# Sheet1.net
KiCad netlist of a schematic drawn in Altium Designer
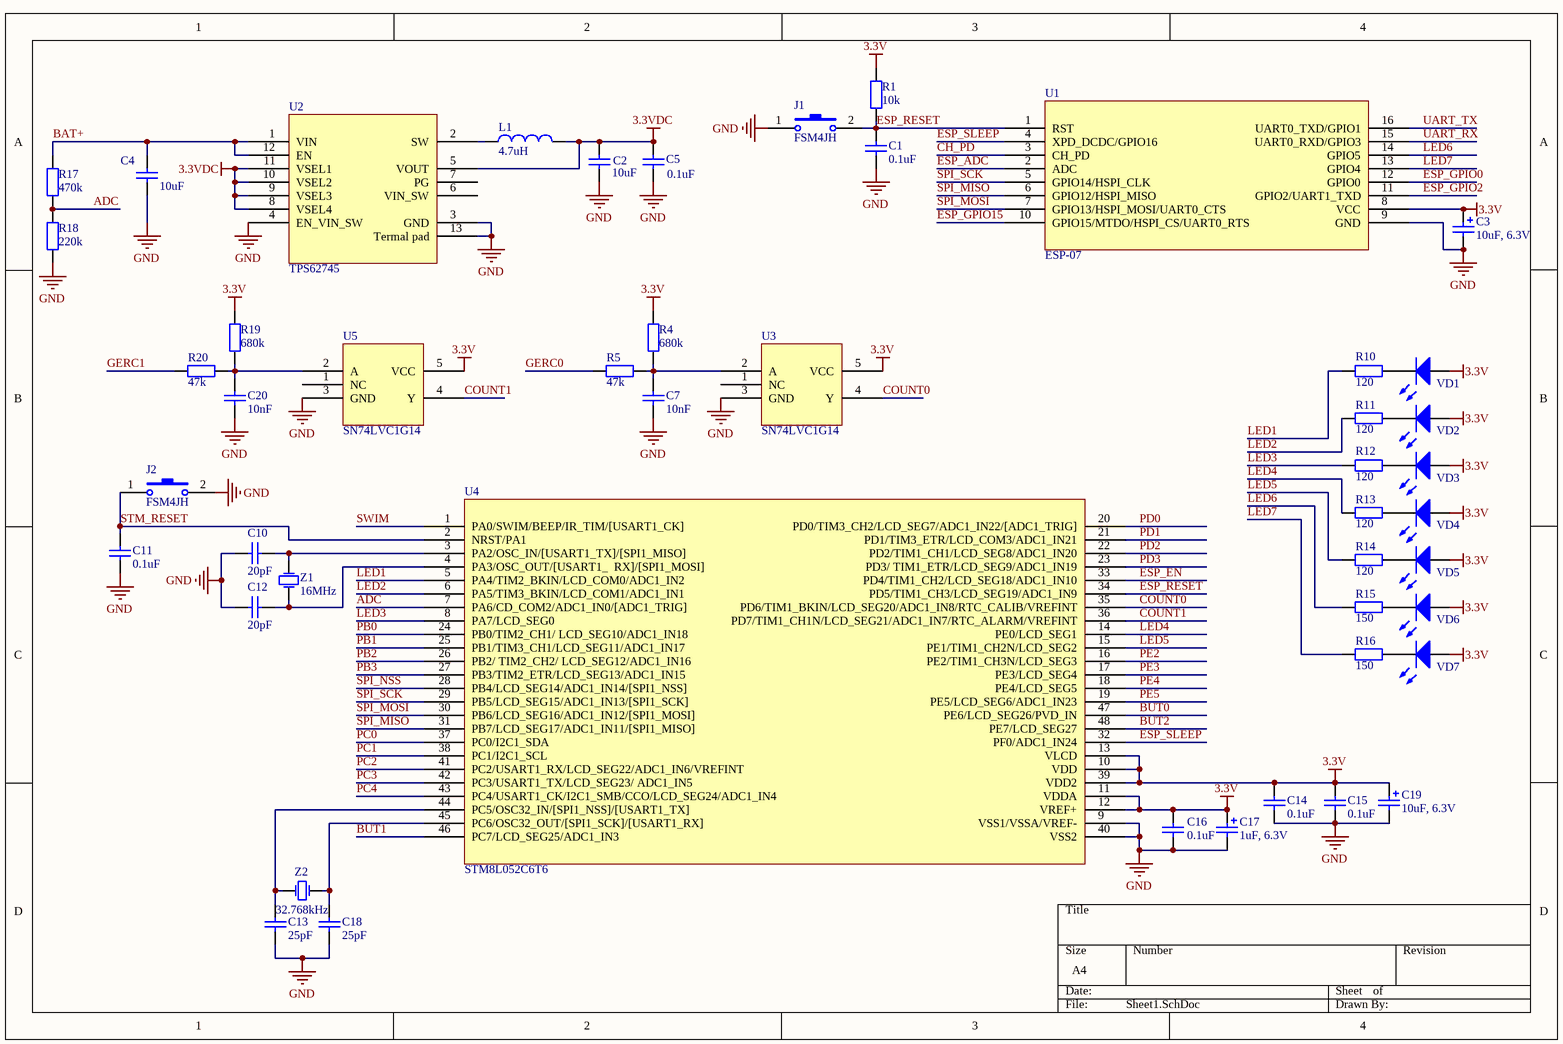
[diagram p0: Sheet1.SchDoc]

(export (version "E")
  (design (tool "Eeschema 10.0.6"))
  (components
    (comp (ref "C1")
      (value "0.1uF")
      (footprint "0603(CAPC1608X09N)")
      (description "Capacitor")
      (libsource (lib "Passive") (part "Capacitor"))
    )
    (comp (ref "C2")
      (value "10uF")
      (footprint "1206(CAPC3216X15N)")
      (description "Capacitor")
      (libsource (lib "Passive") (part "Capacitor"))
    )
    (comp (ref "C3")
      (value "10uF, 6.3V")
      (footprint "1206(typeA)")
      (description "Polarized Capacitor")
      (fields (field (name "Comment") "Capacitor Polarized"))
      (libsource (lib "Passive") (part "Polarized Capacitor"))
    )
    (comp (ref "C4")
      (value "10uF")
      (footprint "1206(CAPC3216X15N)")
      (description "Capacitor")
      (libsource (lib "Passive") (part "Capacitor"))
    )
    (comp (ref "C5")
      (value "0.1uF")
      (footprint "0603(CAPC1608X09N)")
      (description "Capacitor")
      (libsource (lib "Passive") (part "Capacitor"))
    )
    (comp (ref "C7")
      (value "10nF")
      (footprint "0603(CAPC1608X09N)")
      (description "Capacitor")
      (libsource (lib "Passive") (part "Capacitor"))
    )
    (comp (ref "C10")
      (value "20pF")
      (footprint "0603(CAPC1608X09N)")
      (description "Capacitor")
      (libsource (lib "Passive") (part "Capacitor"))
    )
    (comp (ref "C11")
      (value "0.1uF")
      (footprint "0603(CAPC1608X09N)")
      (description "Capacitor")
      (libsource (lib "Passive") (part "Capacitor"))
    )
    (comp (ref "C12")
      (value "20pF")
      (footprint "0603(CAPC1608X09N)")
      (description "Capacitor")
      (libsource (lib "Passive") (part "Capacitor"))
    )
    (comp (ref "C13")
      (value "25pF")
      (footprint "0603(CAPC1608X09N)")
      (description "Capacitor")
      (libsource (lib "Passive") (part "Capacitor"))
    )
    (comp (ref "C14")
      (value "0.1uF")
      (footprint "0603(CAPC1608X09N)")
      (description "Capacitor")
      (libsource (lib "Passive") (part "Capacitor"))
    )
    (comp (ref "C15")
      (value "0.1uF")
      (footprint "0603(CAPC1608X09N)")
      (description "Capacitor")
      (libsource (lib "Passive") (part "Capacitor"))
    )
    (comp (ref "C16")
      (value "0.1uF")
      (footprint "0603(CAPC1608X09N)")
      (description "Capacitor")
      (libsource (lib "Passive") (part "Capacitor"))
    )
    (comp (ref "C17")
      (value "1uF, 6.3V")
      (footprint "1206(typeA)")
      (description "Polarized Capacitor")
      (fields (field (name "Comment") "Capacitor Polarized"))
      (libsource (lib "Passive") (part "Polarized Capacitor"))
    )
    (comp (ref "C18")
      (value "25pF")
      (footprint "0603(CAPC1608X09N)")
      (description "Capacitor")
      (libsource (lib "Passive") (part "Capacitor"))
    )
    (comp (ref "C19")
      (value "10uF, 6.3V")
      (footprint "1206(typeA)")
      (description "Polarized Capacitor")
      (fields (field (name "Comment") "Capacitor Polarized"))
      (libsource (lib "Passive") (part "Polarized Capacitor"))
    )
    (comp (ref "C20")
      (value "10nF")
      (footprint "0603(CAPC1608X09N)")
      (description "Capacitor")
      (libsource (lib "Passive") (part "Capacitor"))
    )
    (comp (ref "J1")
      (value "FSM4JH")
      (footprint "FSM4JH")
      (description "Tact switch")
      (libsource (lib "Schlib1") (part "Tact switch"))
    )
    (comp (ref "J2")
      (value "FSM4JH")
      (footprint "FSM4JH")
      (description "Tact switch")
      (libsource (lib "Schlib1") (part "Tact switch"))
    )
    (comp (ref "L1")
      (value "4.7uH")
      (footprint "0806 (2016)")
      (description "Inductor")
      (libsource (lib "Passive") (part "Inductor"))
    )
    (comp (ref "R1")
      (value "10k")
      (footprint "0603(RESC1608X05N)")
      (description "Resistor")
      (libsource (lib "") (part "Resistor_2"))
    )
    (comp (ref "R4")
      (value "680k")
      (footprint "0603(RESC1608X05N)")
      (description "Resistor")
      (libsource (lib "") (part "Resistor_2"))
    )
    (comp (ref "R5")
      (value "47k")
      (footprint "0603(RESC1608X05N)")
      (description "Resistor")
      (libsource (lib "") (part "Resistor_1"))
    )
    (comp (ref "R10")
      (value "120")
      (footprint "0603(RESC1608X05N)")
      (description "Resistor")
      (libsource (lib "Passive") (part "Resistor"))
    )
    (comp (ref "R11")
      (value "120")
      (footprint "0603(RESC1608X05N)")
      (description "Resistor")
      (libsource (lib "Passive") (part "Resistor"))
    )
    (comp (ref "R12")
      (value "120")
      (footprint "0603(RESC1608X05N)")
      (description "Resistor")
      (libsource (lib "Passive") (part "Resistor"))
    )
    (comp (ref "R13")
      (value "120")
      (footprint "0603(RESC1608X05N)")
      (description "Resistor")
      (libsource (lib "Passive") (part "Resistor"))
    )
    (comp (ref "R14")
      (value "120")
      (footprint "0603(RESC1608X05N)")
      (description "Resistor")
      (libsource (lib "Passive") (part "Resistor"))
    )
    (comp (ref "R15")
      (value "150")
      (footprint "0603(RESC1608X05N)")
      (description "Resistor")
      (libsource (lib "Passive") (part "Resistor"))
    )
    (comp (ref "R16")
      (value "150")
      (footprint "0603(RESC1608X05N)")
      (description "Resistor")
      (libsource (lib "Passive") (part "Resistor"))
    )
    (comp (ref "R17")
      (value "470k")
      (footprint "0603(RESC1608X05N)")
      (description "Resistor")
      (libsource (lib "") (part "Resistor_2"))
    )
    (comp (ref "R18")
      (value "220k")
      (footprint "0603(RESC1608X05N)")
      (description "Resistor")
      (libsource (lib "") (part "Resistor_2"))
    )
    (comp (ref "R19")
      (value "680k")
      (footprint "0603(RESC1608X05N)")
      (description "Resistor")
      (libsource (lib "") (part "Resistor_2"))
    )
    (comp (ref "R20")
      (value "47k")
      (footprint "0603(RESC1608X05N)")
      (description "Resistor")
      (libsource (lib "") (part "Resistor_1"))
    )
    (comp (ref "U1")
      (value "ESP-07")
      (footprint "ESP-07")
      (description "WiFi module")
      (libsource (lib "Schlib1") (part "ESP-07"))
    )
    (comp (ref "U2")
      (value "TPS62745")
      (footprint "12-WSON (3x2)")
      (description "DC/DC step down")
      (fields (field (name "PART NUMBER") "TPS62745DSST") (field (name "MANUFACTURER") "Texas Instruments"))
      (libsource (lib "Schlib1") (part "TPS62745"))
    )
    (comp (ref "U3")
      (value "SN74LVC1G14")
      (footprint "SOT23-5")
      (description "Single SchmittT-Trigger Inverter")
      (fields
        (field (name "PART NUMBER") "SN74LVC1G14DBVR")
        (field (name "MANUFACTURER") "Texas Instruments")
      )
      (libsource (lib "Schlib1") (part "SN74LVC1G14"))
    )
    (comp (ref "U4")
      (value "STM8L052C6T6")
      (footprint "LQFP-48")
      (description "MCU")
      (fields (field (name "MANUFACTURER") "STMicroelectronics"))
      (libsource (lib "Schlib1") (part "STM8L052C6"))
    )
    (comp (ref "U5")
      (value "SN74LVC1G14")
      (footprint "SOT23-5")
      (description "Single SchmittT-Trigger Inverter")
      (fields
        (field (name "PART NUMBER") "SN74LVC1G14DBVR")
        (field (name "MANUFACTURER") "Texas Instruments")
      )
      (libsource (lib "Schlib1") (part "SN74LVC1G14"))
    )
    (comp (ref "VD1")
      (value "Led")
      (footprint "GNL-3014xx")
      (description "Светодиод")
      (libsource (lib "Passive") (part "Led"))
    )
    (comp (ref "VD2")
      (value "Led")
      (footprint "GNL-3014xx")
      (description "Светодиод")
      (libsource (lib "Passive") (part "Led"))
    )
    (comp (ref "VD3")
      (value "Led")
      (footprint "GNL-3014xx")
      (description "Светодиод")
      (libsource (lib "Passive") (part "Led"))
    )
    (comp (ref "VD4")
      (value "Led")
      (footprint "GNL-3014xx")
      (description "Светодиод")
      (libsource (lib "Passive") (part "Led"))
    )
    (comp (ref "VD5")
      (value "Led")
      (footprint "GNL-3014xx")
      (description "Светодиод")
      (libsource (lib "Passive") (part "Led"))
    )
    (comp (ref "VD6")
      (value "Led")
      (footprint "GNL-3014xx")
      (description "Светодиод")
      (libsource (lib "Passive") (part "Led"))
    )
    (comp (ref "VD7")
      (value "Led")
      (footprint "GNL-3014xx")
      (description "Светодиод")
      (libsource (lib "Passive") (part "Led"))
    )
    (comp (ref "Z1")
      (value "16MHz")
      (footprint "HC49S")
      (description "Crystal Oscillator")
      (libsource (lib "Passive") (part "Crystal"))
    )
    (comp (ref "Z2")
      (value "32.768kHz")
      (footprint "KX–327NHT")
      (description "Crystal Oscillator")
      (libsource (lib "Passive") (part "Crystal"))
    )
  )
  (nets
    (net (code "1") (name "/ADC") (class "Default")
      (node (ref "R17") (pin "1") (pinfunction "1_1") (pintype "passive"))
      (node (ref "R18") (pin "2") (pinfunction "2_2") (pintype "passive"))
      (node (ref "U4") (pin "7") (pinfunction "PA6/CD_COM2/ADC1_IN0/[ADC1_TRIG]_7") (pintype "passive"))
    )
    (net (code "2") (name "/BAT+") (class "Default")
      (node (ref "C4") (pin "1") (pinfunction "1_1") (pintype "passive"))
      (node (ref "R17") (pin "2") (pinfunction "2_2") (pintype "passive"))
      (node (ref "U2") (pin "1") (pinfunction "VIN_1") (pintype "passive"))
      (node (ref "U2") (pin "12") (pinfunction "EN_12") (pintype "passive"))
    )
    (net (code "3") (name "/BUT0") (class "Default")
      (node (ref "U4") (pin "47") (pinfunction "PE6/LCD_SEG26/PVD_IN_47") (pintype "passive"))
    )
    (net (code "4") (name "/BUT1") (class "Default")
      (node (ref "U4") (pin "46") (pinfunction "PC7/LCD_SEG25/ADC1_IN3_46") (pintype "passive"))
    )
    (net (code "5") (name "/BUT2") (class "Default")
      (node (ref "U4") (pin "48") (pinfunction "PE7/LCD_SEG27_48") (pintype "passive"))
    )
    (net (code "6") (name "/CH_PD") (class "Default")
      (node (ref "U1") (pin "3") (pinfunction "CH_PD_3") (pintype "passive"))
    )
    (net (code "7") (name "/COUNT0") (class "Default")
      (node (ref "U3") (pin "4") (pinfunction "Y_4") (pintype "passive"))
      (node (ref "U4") (pin "35") (pinfunction "PD6/TIM1_BKIN/LCD_SEG20/ADC1_IN8/RTC_CALIB/VREFINT_35") (pintype "passive"))
    )
    (net (code "8") (name "/COUNT1") (class "Default")
      (node (ref "U4") (pin "36") (pinfunction "PD7/TIM1_CH1N/LCD_SEG21/ADC1_IN7/RTC_ALARM/VREFINT_36") (pintype "passive"))
      (node (ref "U5") (pin "4") (pinfunction "Y_4") (pintype "passive"))
    )
    (net (code "9") (name "/ESP_ADC") (class "Default")
      (node (ref "U1") (pin "2") (pinfunction "ADC_2") (pintype "passive"))
    )
    (net (code "10") (name "/ESP_EN") (class "Default")
      (node (ref "U4") (pin "33") (pinfunction "PD4/TIM1_CH2/LCD_SEG18/ADC1_IN10_33") (pintype "passive"))
    )
    (net (code "11") (name "/ESP_GPIO0") (class "Default")
      (node (ref "U1") (pin "12") (pinfunction "GPIO0_12") (pintype "passive"))
    )
    (net (code "12") (name "/ESP_GPIO2") (class "Default")
      (node (ref "U1") (pin "11") (pinfunction "GPIO2/UART1_TXD_11") (pintype "passive"))
    )
    (net (code "13") (name "/ESP_GPIO15") (class "Default")
      (node (ref "U1") (pin "10") (pinfunction "GPIO15/MTDO/HSPI_CS/UART0_RTS_10") (pintype "passive"))
    )
    (net (code "14") (name "/ESP_RESET") (class "Default")
      (node (ref "C1") (pin "2") (pinfunction "2_2") (pintype "passive"))
      (node (ref "J1") (pin "2") (pinfunction "NO1_2") (pintype "passive"))
      (node (ref "R1") (pin "1") (pinfunction "1_1") (pintype "passive"))
      (node (ref "U1") (pin "1") (pinfunction "RST_1") (pintype "passive"))
      (node (ref "U4") (pin "34") (pinfunction "PD5/TIM1_CH3/LCD_SEG19/ADC1_IN9_34") (pintype "passive"))
    )
    (net (code "15") (name "/ESP_SLEEP") (class "Default")
      (node (ref "U1") (pin "4") (pinfunction "XPD_DCDC/GPIO16_4") (pintype "passive"))
      (node (ref "U4") (pin "32") (pinfunction "PF0/ADC1_IN24_32") (pintype "passive"))
    )
    (net (code "16") (name "/GERC0") (class "Default")
      (node (ref "R5") (pin "2") (pinfunction "2_2") (pintype "passive"))
    )
    (net (code "17") (name "/GERC1") (class "Default")
      (node (ref "R20") (pin "2") (pinfunction "2_2") (pintype "passive"))
    )
    (net (code "18") (name "/LED1") (class "Default")
      (node (ref "R10") (pin "1") (pinfunction "1_1") (pintype "passive"))
      (node (ref "U4") (pin "5") (pinfunction "PA4/TIM2_BKIN/LCD_COM0/ADC1_IN2_5") (pintype "passive"))
    )
    (net (code "19") (name "/LED2") (class "Default")
      (node (ref "R11") (pin "1") (pinfunction "1_1") (pintype "passive"))
      (node (ref "U4") (pin "6") (pinfunction "PA5/TIM3_BKIN/LCD_COM1/ADC1_IN1_6") (pintype "passive"))
    )
    (net (code "20") (name "/LED3") (class "Default")
      (node (ref "R12") (pin "1") (pinfunction "1_1") (pintype "passive"))
      (node (ref "U4") (pin "8") (pinfunction "PA7/LCD_SEG0_8") (pintype "passive"))
    )
    (net (code "21") (name "/LED4") (class "Default")
      (node (ref "R13") (pin "1") (pinfunction "1_1") (pintype "passive"))
      (node (ref "U4") (pin "14") (pinfunction "PE0/LCD_SEG1_14") (pintype "passive"))
    )
    (net (code "22") (name "/LED5") (class "Default")
      (node (ref "R14") (pin "1") (pinfunction "1_1") (pintype "passive"))
      (node (ref "U4") (pin "15") (pinfunction "PE1/TIM1_CH2N/LCD_SEG2_15") (pintype "passive"))
    )
    (net (code "23") (name "/LED6") (class "Default")
      (node (ref "R15") (pin "1") (pinfunction "1_1") (pintype "passive"))
      (node (ref "U1") (pin "14") (pinfunction "GPIO5_14") (pintype "passive"))
    )
    (net (code "24") (name "/LED7") (class "Default")
      (node (ref "R16") (pin "1") (pinfunction "1_1") (pintype "passive"))
      (node (ref "U1") (pin "13") (pinfunction "GPIO4_13") (pintype "passive"))
    )
    (net (code "25") (name "/PB0") (class "Default")
      (node (ref "U4") (pin "24") (pinfunction "PB0/TIM2_CH1/_LCD_SEG10/ADC1_IN18_24") (pintype "passive"))
    )
    (net (code "26") (name "/PB1") (class "Default")
      (node (ref "U4") (pin "25") (pinfunction "PB1/TIM3_CH1/LCD_SEG11/ADC1_IN17_25") (pintype "passive"))
    )
    (net (code "27") (name "/PB2") (class "Default")
      (node (ref "U4") (pin "26") (pinfunction "PB2/_TIM2_CH2/_LCD_SEG12/ADC1_IN16_26") (pintype "passive"))
    )
    (net (code "28") (name "/PB3") (class "Default")
      (node (ref "U4") (pin "27") (pinfunction "PB3/TIM2_ETR/LCD_SEG13/ADC1_IN15_27") (pintype "passive"))
    )
    (net (code "29") (name "/PC0") (class "Default")
      (node (ref "U4") (pin "37") (pinfunction "PC0/I2C1_SDA_37") (pintype "passive"))
    )
    (net (code "30") (name "/PC1") (class "Default")
      (node (ref "U4") (pin "38") (pinfunction "PC1/I2C1_SCL_38") (pintype "passive"))
    )
    (net (code "31") (name "/PC2") (class "Default")
      (node (ref "U4") (pin "41") (pinfunction "PC2/USART1_RX/LCD_SEG22/ADC1_IN6/VREFINT_41") (pintype "passive"))
    )
    (net (code "32") (name "/PC3") (class "Default")
      (node (ref "U4") (pin "42") (pinfunction "PC3/USART1_TX/LCD_SEG23/_ADC1_IN5_42") (pintype "passive"))
    )
    (net (code "33") (name "/PC4") (class "Default")
      (node (ref "U4") (pin "43") (pinfunction "PC4/USART1_CK/I2C1_SMB/CCO/LCD_SEG24/ADC1_IN4_43") (pintype "passive"))
    )
    (net (code "34") (name "/PD0") (class "Default")
      (node (ref "U4") (pin "20") (pinfunction "PD0/TIM3_CH2/LCD_SEG7/ADC1_IN22/[ADC1_TRIG]_20") (pintype "passive"))
    )
    (net (code "35") (name "/PD1") (class "Default")
      (node (ref "U4") (pin "21") (pinfunction "PD1/TIM3_ETR/LCD_COM3/ADC1_IN21_21") (pintype "passive"))
    )
    (net (code "36") (name "/PD2") (class "Default")
      (node (ref "U4") (pin "22") (pinfunction "PD2/TIM1_CH1/LCD_SEG8/ADC1_IN20_22") (pintype "passive"))
    )
    (net (code "37") (name "/PD3") (class "Default")
      (node (ref "U4") (pin "23") (pinfunction "PD3/_TIM1_ETR/LCD_SEG9/ADC1_IN19_23") (pintype "passive"))
    )
    (net (code "38") (name "/PE2") (class "Default")
      (node (ref "U4") (pin "16") (pinfunction "PE2/TIM1_CH3N/LCD_SEG3_16") (pintype "passive"))
    )
    (net (code "39") (name "/PE3") (class "Default")
      (node (ref "U4") (pin "17") (pinfunction "PE3/LCD_SEG4_17") (pintype "passive"))
    )
    (net (code "40") (name "/PE4") (class "Default")
      (node (ref "U4") (pin "18") (pinfunction "PE4/LCD_SEG5_18") (pintype "passive"))
    )
    (net (code "41") (name "/PE5") (class "Default")
      (node (ref "U4") (pin "19") (pinfunction "PE5/LCD_SEG6/ADC1_IN23_19") (pintype "passive"))
    )
    (net (code "42") (name "/SPI_MISO") (class "Default")
      (node (ref "U1") (pin "6") (pinfunction "GPIO12/HSPI_MISO_6") (pintype "passive"))
      (node (ref "U4") (pin "31") (pinfunction "PB7/LCD_SEG17/ADC1_IN11/[SPI1_MISO]_31") (pintype "passive"))
    )
    (net (code "43") (name "/SPI_MOSI") (class "Default")
      (node (ref "U1") (pin "7") (pinfunction "GPIO13/HSPI_MOSI/UART0_CTS_7") (pintype "passive"))
      (node (ref "U4") (pin "30") (pinfunction "PB6/LCD_SEG16/ADC1_IN12/[SPI1_MOSI]_30") (pintype "passive"))
    )
    (net (code "44") (name "/SPI_NSS") (class "Default")
      (node (ref "U4") (pin "28") (pinfunction "PB4/LCD_SEG14/ADC1_IN14/[SPI1_NSS]_28") (pintype "passive"))
    )
    (net (code "45") (name "/SPI_SCK") (class "Default")
      (node (ref "U1") (pin "5") (pinfunction "GPIO14/HSPI_CLK_5") (pintype "passive"))
      (node (ref "U4") (pin "29") (pinfunction "PB5/LCD_SEG15/ADC1_IN13/[SPI1_SCK]_29") (pintype "passive"))
    )
    (net (code "46") (name "/STM_RESET") (class "Default")
      (node (ref "C11") (pin "2") (pinfunction "2_2") (pintype "passive"))
      (node (ref "J2") (pin "1") (pinfunction "COMMON1_1") (pintype "passive"))
      (node (ref "U4") (pin "2") (pinfunction "NRST/PA1_2") (pintype "passive"))
    )
    (net (code "47") (name "/SWIM") (class "Default")
      (node (ref "U4") (pin "1") (pinfunction "PA0/SWIM/BEEP/IR_TIM/[USART1_CK]_1") (pintype "passive"))
    )
    (net (code "48") (name "/UART_RX") (class "Default")
      (node (ref "U1") (pin "15") (pinfunction "UART0_RXD/GPIO3_15") (pintype "passive"))
    )
    (net (code "49") (name "/UART_TX") (class "Default")
      (node (ref "U1") (pin "16") (pinfunction "UART0_TXD/GPIO1_16") (pintype "passive"))
    )
    (net (code "50") (name "3.3V") (class "Default")
      (node (ref "C14") (pin "2") (pinfunction "2_2") (pintype "passive"))
      (node (ref "C15") (pin "2") (pinfunction "2_2") (pintype "passive"))
      (node (ref "C16") (pin "1") (pinfunction "1_1") (pintype "passive"))
      (node (ref "C17") (pin "1") (pinfunction "1_1") (pintype "passive"))
      (node (ref "C19") (pin "1") (pinfunction "1_1") (pintype "passive"))
      (node (ref "C3") (pin "1") (pinfunction "1_1") (pintype "passive"))
      (node (ref "R1") (pin "2") (pinfunction "2_2") (pintype "passive"))
      (node (ref "R19") (pin "2") (pinfunction "2_2") (pintype "passive"))
      (node (ref "R4") (pin "2") (pinfunction "2_2") (pintype "passive"))
      (node (ref "U1") (pin "8") (pinfunction "VCC_8") (pintype "passive"))
      (node (ref "U3") (pin "5") (pinfunction "VCC_5") (pintype "passive"))
      (node (ref "U4") (pin "10") (pinfunction "VDD_10") (pintype "passive"))
      (node (ref "U4") (pin "11") (pinfunction "VDDA_11") (pintype "passive"))
      (node (ref "U4") (pin "12") (pinfunction "VREF+_12") (pintype "passive"))
      (node (ref "U4") (pin "13") (pinfunction "VLCD_13") (pintype "passive"))
      (node (ref "U4") (pin "39") (pinfunction "VDD2_39") (pintype "passive"))
      (node (ref "U5") (pin "5") (pinfunction "VCC_5") (pintype "passive"))
      (node (ref "VD1") (pin "1") (pinfunction "A_1") (pintype "passive"))
      (node (ref "VD2") (pin "1") (pinfunction "A_1") (pintype "passive"))
      (node (ref "VD3") (pin "1") (pinfunction "A_1") (pintype "passive"))
      (node (ref "VD4") (pin "1") (pinfunction "A_1") (pintype "passive"))
      (node (ref "VD5") (pin "1") (pinfunction "A_1") (pintype "passive"))
      (node (ref "VD6") (pin "1") (pinfunction "A_1") (pintype "passive"))
      (node (ref "VD7") (pin "1") (pinfunction "A_1") (pintype "passive"))
    )
    (net (code "51") (name "3.3VDC") (class "Default")
      (node (ref "C2") (pin "2") (pinfunction "2_2") (pintype "passive"))
      (node (ref "C5") (pin "2") (pinfunction "2_2") (pintype "passive"))
      (node (ref "L1") (pin "1") (pinfunction "1_1") (pintype "passive"))
      (node (ref "U2") (pin "10") (pinfunction "VSEL2_10") (pintype "passive"))
      (node (ref "U2") (pin "11") (pinfunction "VSEL1_11") (pintype "passive"))
      (node (ref "U2") (pin "5") (pinfunction "VOUT_5") (pintype "passive"))
      (node (ref "U2") (pin "8") (pinfunction "VSEL4_8") (pintype "passive"))
      (node (ref "U2") (pin "9") (pinfunction "VSEL3_9") (pintype "passive"))
    )
    (net (code "52") (name "GND") (class "Default")
      (node (ref "C1") (pin "1") (pinfunction "1_1") (pintype "passive"))
      (node (ref "C10") (pin "1") (pinfunction "1_1") (pintype "passive"))
      (node (ref "C11") (pin "1") (pinfunction "1_1") (pintype "passive"))
      (node (ref "C12") (pin "1") (pinfunction "1_1") (pintype "passive"))
      (node (ref "C13") (pin "1") (pinfunction "1_1") (pintype "passive"))
      (node (ref "C14") (pin "1") (pinfunction "1_1") (pintype "passive"))
      (node (ref "C15") (pin "1") (pinfunction "1_1") (pintype "passive"))
      (node (ref "C16") (pin "2") (pinfunction "2_2") (pintype "passive"))
      (node (ref "C17") (pin "2") (pinfunction "2_2") (pintype "passive"))
      (node (ref "C18") (pin "1") (pinfunction "1_1") (pintype "passive"))
      (node (ref "C19") (pin "2") (pinfunction "2_2") (pintype "passive"))
      (node (ref "C2") (pin "1") (pinfunction "1_1") (pintype "passive"))
      (node (ref "C20") (pin "1") (pinfunction "1_1") (pintype "passive"))
      (node (ref "C3") (pin "2") (pinfunction "2_2") (pintype "passive"))
      (node (ref "C4") (pin "2") (pinfunction "2_2") (pintype "passive"))
      (node (ref "C5") (pin "1") (pinfunction "1_1") (pintype "passive"))
      (node (ref "C7") (pin "1") (pinfunction "1_1") (pintype "passive"))
      (node (ref "J1") (pin "1") (pinfunction "COMMON1_1") (pintype "passive"))
      (node (ref "J2") (pin "2") (pinfunction "NO1_2") (pintype "passive"))
      (node (ref "R18") (pin "1") (pinfunction "1_1") (pintype "passive"))
      (node (ref "U1") (pin "9") (pinfunction "GND_9") (pintype "passive"))
      (node (ref "U2") (pin "13") (pinfunction "Termal_pad_13") (pintype "passive"))
      (node (ref "U2") (pin "3") (pinfunction "GND_3") (pintype "passive"))
      (node (ref "U2") (pin "4") (pinfunction "EN_VIN_SW_4") (pintype "passive"))
      (node (ref "U3") (pin "3") (pinfunction "GND_3") (pintype "passive"))
      (node (ref "U4") (pin "40") (pinfunction "VSS2_40") (pintype "passive"))
      (node (ref "U4") (pin "9") (pinfunction "VSS1/VSSA/VREF-_9") (pintype "passive"))
      (node (ref "U5") (pin "3") (pinfunction "GND_3") (pintype "passive"))
    )
    (net (code "53") (name "Net-(U2-SW)") (class "Default")
      (node (ref "L1") (pin "2") (pinfunction "2_2") (pintype "passive"))
      (node (ref "U2") (pin "2") (pinfunction "SW_2") (pintype "passive"))
    )
    (net (code "54") (name "Net-(U3-A)") (class "Default")
      (node (ref "C7") (pin "2") (pinfunction "2_2") (pintype "passive"))
      (node (ref "R4") (pin "1") (pinfunction "1_1") (pintype "passive"))
      (node (ref "R5") (pin "1") (pinfunction "1_1") (pintype "passive"))
      (node (ref "U3") (pin "2") (pinfunction "A_2") (pintype "passive"))
    )
    (net (code "55") (name "Net-(U4-PA2{slash}OSC_IN{slash}[USART1_TX]{slash}[SPI1_MISO])") (class "Default")
      (node (ref "C10") (pin "2") (pinfunction "2_2") (pintype "passive"))
      (node (ref "U4") (pin "3") (pinfunction "PA2/OSC_IN/[USART1_TX]/[SPI1_MISO]_3") (pintype "passive"))
      (node (ref "Z1") (pin "2") (pinfunction "OSC2_2") (pintype "passive"))
    )
    (net (code "56") (name "Net-(U4-PA3{slash}OSC_OUT{slash}[USART1___RX]{slash}[SPI1_MOSI])") (class "Default")
      (node (ref "C12") (pin "2") (pinfunction "2_2") (pintype "passive"))
      (node (ref "U4") (pin "4") (pinfunction "PA3/OSC_OUT/[USART1___RX]/[SPI1_MOSI]_4") (pintype "passive"))
      (node (ref "Z1") (pin "1") (pinfunction "OSC1_1") (pintype "passive"))
    )
    (net (code "57") (name "Net-(U4-PC5{slash}OSC32_IN{slash}[SPI1_NSS]{slash}[USART1_TX])") (class "Default")
      (node (ref "C13") (pin "2") (pinfunction "2_2") (pintype "passive"))
      (node (ref "U4") (pin "44") (pinfunction "PC5/OSC32_IN/[SPI1_NSS]/[USART1_TX]_44") (pintype "passive"))
      (node (ref "Z2") (pin "2") (pinfunction "OSC2_2") (pintype "passive"))
    )
    (net (code "58") (name "Net-(U4-PC6{slash}OSC32_OUT{slash}[SPI1_SCK]{slash}[USART1_RX])") (class "Default")
      (node (ref "C18") (pin "2") (pinfunction "2_2") (pintype "passive"))
      (node (ref "U4") (pin "45") (pinfunction "PC6/OSC32_OUT/[SPI1_SCK]/[USART1_RX]_45") (pintype "passive"))
      (node (ref "Z2") (pin "1") (pinfunction "OSC1_1") (pintype "passive"))
    )
    (net (code "59") (name "Net-(U5-A)") (class "Default")
      (node (ref "C20") (pin "2") (pinfunction "2_2") (pintype "passive"))
      (node (ref "R19") (pin "1") (pinfunction "1_1") (pintype "passive"))
      (node (ref "R20") (pin "1") (pinfunction "1_1") (pintype "passive"))
      (node (ref "U5") (pin "2") (pinfunction "A_2") (pintype "passive"))
    )
    (net (code "60") (name "Net-(VD1-K)") (class "Default")
      (node (ref "R10") (pin "2") (pinfunction "2_2") (pintype "passive"))
      (node (ref "VD1") (pin "2") (pinfunction "K_2") (pintype "passive"))
    )
    (net (code "61") (name "Net-(VD2-K)") (class "Default")
      (node (ref "R11") (pin "2") (pinfunction "2_2") (pintype "passive"))
      (node (ref "VD2") (pin "2") (pinfunction "K_2") (pintype "passive"))
    )
    (net (code "62") (name "Net-(VD3-K)") (class "Default")
      (node (ref "R12") (pin "2") (pinfunction "2_2") (pintype "passive"))
      (node (ref "VD3") (pin "2") (pinfunction "K_2") (pintype "passive"))
    )
    (net (code "63") (name "Net-(VD4-K)") (class "Default")
      (node (ref "R13") (pin "2") (pinfunction "2_2") (pintype "passive"))
      (node (ref "VD4") (pin "2") (pinfunction "K_2") (pintype "passive"))
    )
    (net (code "64") (name "Net-(VD5-K)") (class "Default")
      (node (ref "R14") (pin "2") (pinfunction "2_2") (pintype "passive"))
      (node (ref "VD5") (pin "2") (pinfunction "K_2") (pintype "passive"))
    )
    (net (code "65") (name "Net-(VD6-K)") (class "Default")
      (node (ref "R15") (pin "2") (pinfunction "2_2") (pintype "passive"))
      (node (ref "VD6") (pin "2") (pinfunction "K_2") (pintype "passive"))
    )
    (net (code "66") (name "Net-(VD7-K)") (class "Default")
      (node (ref "R16") (pin "2") (pinfunction "2_2") (pintype "passive"))
      (node (ref "VD7") (pin "2") (pinfunction "K_2") (pintype "passive"))
    )
    (net (code "67") (name "unconnected-(U2-PG-Pad7)") (class "Default")
      (node (ref "U2") (pin "7") (pinfunction "PG_7") (pintype "passive"))
    )
    (net (code "68") (name "unconnected-(U2-VIN_SW-Pad6)") (class "Default")
      (node (ref "U2") (pin "6") (pinfunction "VIN_SW_6") (pintype "passive"))
    )
    (net (code "69") (name "unconnected-(U3-NC-Pad1)") (class "Default")
      (node (ref "U3") (pin "1") (pinfunction "NC_1") (pintype "passive"))
    )
    (net (code "70") (name "unconnected-(U5-NC-Pad1)") (class "Default")
      (node (ref "U5") (pin "1") (pinfunction "NC_1") (pintype "passive"))
    )
  )
)
